# 4G_CAT1_CN4N40.net
KiCad netlist of a schematic drawn in Altium Designer
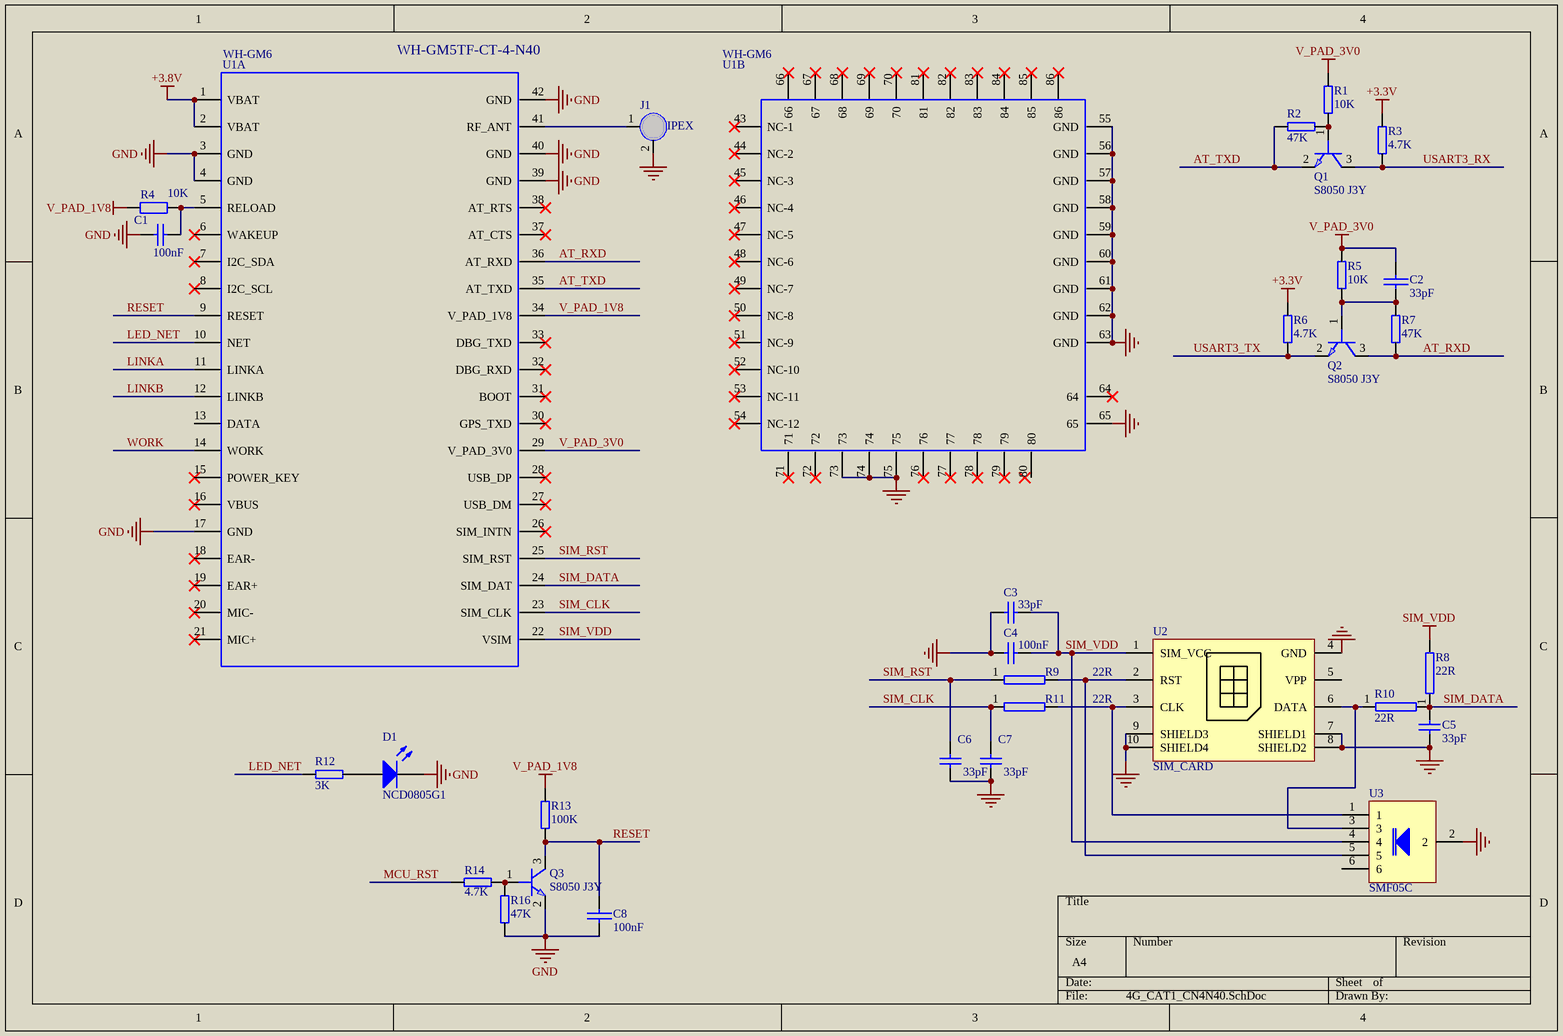
[diagram p0: 4G_CAT1_CN4N40.SchDoc]

(export (version "E")
  (design (tool "Eeschema 10.0.6"))
  (components
    (comp (ref "C1")
      (value "100nF")
      (footprint "LC-0805_C")
      (description "Capacitor")
      (fields (field (name "PUBLISHER") "Altium Limited"))
      (libsource (lib "*") (part "CAP"))
    )
    (comp (ref "C2")
      (value "33pF")
      (footprint "LC-0805_C")
      (description "Capacitor")
      (libsource (lib "") (part "CAP_1"))
    )
    (comp (ref "C3")
      (value "33pF")
      (footprint "LC-0805_C")
      (description "Capacitor")
      (fields (field (name "PUBLISHER") "Altium Limited"))
      (libsource (lib "*") (part "CAP"))
    )
    (comp (ref "C4")
      (value "100nF")
      (footprint "LC-0805_C")
      (description "Capacitor")
      (fields (field (name "PUBLISHER") "Altium Limited"))
      (libsource (lib "*") (part "CAP"))
    )
    (comp (ref "C5")
      (value "33pF")
      (footprint "LC-0805_C")
      (description "Capacitor")
      (fields (field (name "PUBLISHER") "Altium Limited"))
      (libsource (lib "*") (part "CAP"))
    )
    (comp (ref "C6")
      (value "33pF")
      (footprint "LC-0805_C")
      (description "Capacitor")
      (fields (field (name "PUBLISHER") "Altium Limited"))
      (libsource (lib "*") (part "CAP"))
    )
    (comp (ref "C7")
      (value "33pF")
      (footprint "LC-0805_C")
      (description "Capacitor")
      (fields (field (name "PUBLISHER") "Altium Limited"))
      (libsource (lib "*") (part "CAP"))
    )
    (comp (ref "C8")
      (value "100nF")
      (footprint "LC-0805_C")
      (description "Capacitor")
      (libsource (lib "") (part "CAP_1"))
    )
    (comp (ref "D1")
      (value "NCD0805G1")
      (footprint "LC-0805_LED_S1")
      (description "Typical RED, GREEN, YELLOW, AMBER GaAs LED")
      (fields (field (name "PUBLISHER") "Altium Limited"))
      (libsource (lib "Miscellaneous Devices") (part "LED2"))
    )
    (comp (ref "J1") (value "IPEX") (footprint "ANT-TH_KH-SMA-K513-G") (libsource (lib "NEW") (part "IPEX")))
    (comp (ref "Q1") (value "S8050 J3Y") (footprint "SOT-23") (libsource (lib "*") (part "2N5551")))
    (comp (ref "Q2") (value "S8050 J3Y") (footprint "SOT-23") (libsource (lib "*") (part "2N5551")))
    (comp (ref "Q3") (value "S8050 J3Y") (footprint "SOT-23") (libsource (lib "*") (part "2N5551")))
    (comp (ref "R1")
      (value "10K")
      (footprint "LC-0805_R")
      (description "1K")
      (libsource (lib "*") (part "RES22"))
    )
    (comp (ref "R2")
      (value "47K")
      (footprint "LC-0805_R")
      (description "1K")
      (libsource (lib "*") (part "RES22"))
    )
    (comp (ref "R3")
      (value "4.7K")
      (footprint "LC-0805_R")
      (description "1K")
      (libsource (lib "*") (part "RES22"))
    )
    (comp (ref "R4")
      (value "10K")
      (footprint "LC-0805_R")
      (description "Resistor")
      (fields (field (name "PUBLISHER") "Altium Limited"))
      (libsource (lib "Miscellaneous Devices") (part "Res2"))
    )
    (comp (ref "R5")
      (value "10K")
      (footprint "LC-0805_R")
      (description "1K")
      (libsource (lib "*") (part "RES22"))
    )
    (comp (ref "R6")
      (value "4.7K")
      (footprint "LC-0805_R")
      (description "1K")
      (libsource (lib "*") (part "RES22"))
    )
    (comp (ref "R7")
      (value "47K")
      (footprint "LC-0805_R")
      (description "1K")
      (libsource (lib "*") (part "RES22"))
    )
    (comp (ref "R8") (value "22R") (footprint "LC-0805_R") (libsource (lib "*") (part "RES2")))
    (comp (ref "R9") (value "22R") (footprint "LC-0805_R") (libsource (lib "*") (part "RES2")))
    (comp (ref "R10") (value "22R") (footprint "LC-0805_R") (libsource (lib "*") (part "RES2")))
    (comp (ref "R11") (value "22R") (footprint "LC-0805_R") (libsource (lib "*") (part "RES2")))
    (comp (ref "R12")
      (value "3K")
      (footprint "LC-0805_R")
      (description "1K")
      (libsource (lib "*") (part "RES22"))
    )
    (comp (ref "R13")
      (value "100K")
      (footprint "LC-0805_R")
      (description "1K")
      (libsource (lib "*") (part "RES22"))
    )
    (comp (ref "R14")
      (value "4.7K")
      (footprint "LC-0805_R")
      (description "1K")
      (libsource (lib "*") (part "RES22"))
    )
    (comp (ref "R16")
      (value "47K")
      (footprint "LC-0805_R")
      (description "1K")
      (libsource (lib "*") (part "RES22"))
    )
    (comp (ref "U1") (value "WH-GM6") (footprint "WH-GM6") (libsource (lib "WH-GM5TF-8-N40") (part "WH-GM6")))
    (comp (ref "U2")
      (value "SIM_CARD")
      (footprint "SIM_MICRO_6P")
      (libsource (lib "PCB_Project_gprs") (part "SIM_CARD"))
    )
    (comp (ref "U3") (value "SMF05C") (footprint "SOT-363") (libsource (lib "NEW") (part "SMF05C")))
  )
  (nets
    (net (code "1") (name "+3.3V") (class "Default")
      (node (ref "R3") (pin "1") (pintype "passive"))
      (node (ref "R6") (pin "1") (pintype "passive"))
    )
    (net (code "2") (name "+3.8V") (class "Default")
      (node (ref "U1") (pin "1") (pinfunction "VBAT_1") (pintype "passive"))
      (node (ref "U1") (pin "2") (pinfunction "VBAT_2") (pintype "passive"))
    )
    (net (code "3") (name "/AT_RXD") (class "Default")
      (node (ref "Q2") (pin "3") (pinfunction "C_3") (pintype "passive"))
      (node (ref "R7") (pin "1") (pintype "passive"))
      (node (ref "U1") (pin "36") (pinfunction "AT_RXD_36") (pintype "passive"))
    )
    (net (code "4") (name "/AT_TXD") (class "Default")
      (node (ref "Q1") (pin "2") (pinfunction "E_2") (pintype "passive"))
      (node (ref "R2") (pin "1") (pintype "passive"))
      (node (ref "U1") (pin "35") (pinfunction "AT_TXD_35") (pintype "passive"))
    )
    (net (code "5") (name "/LED_NET") (class "Default")
      (node (ref "R12") (pin "2") (pintype "passive"))
      (node (ref "U1") (pin "10") (pinfunction "NET_10") (pintype "passive"))
    )
    (net (code "6") (name "/LINKA") (class "Default")
      (node (ref "U1") (pin "11") (pinfunction "LINKA_11") (pintype "passive"))
    )
    (net (code "7") (name "/LINKB") (class "Default")
      (node (ref "U1") (pin "12") (pinfunction "LINKB_12") (pintype "passive"))
    )
    (net (code "8") (name "/MCU_RST") (class "Default") (node (ref "R14") (pin "1") (pintype "passive")))
    (net (code "9") (name "/RESET") (class "Default")
      (node (ref "C8") (pin "1") (pinfunction "1_1") (pintype "passive"))
      (node (ref "Q3") (pin "3") (pinfunction "C_3") (pintype "passive"))
      (node (ref "R13") (pin "1") (pintype "passive"))
      (node (ref "U1") (pin "9") (pinfunction "RESET_9") (pintype "passive"))
    )
    (net (code "10") (name "/SIM_CLK") (class "Default")
      (node (ref "C7") (pin "1") (pinfunction "1_1") (pintype "passive"))
      (node (ref "R11") (pin "1") (pintype "passive"))
      (node (ref "U1") (pin "23") (pinfunction "SIM_CLK_23") (pintype "passive"))
    )
    (net (code "11") (name "/SIM_DATA") (class "Default")
      (node (ref "C5") (pin "1") (pinfunction "1_1") (pintype "passive"))
      (node (ref "R10") (pin "2") (pintype "passive"))
      (node (ref "R8") (pin "1") (pintype "passive"))
      (node (ref "U1") (pin "24") (pinfunction "SIM_DAT_24") (pintype "passive"))
    )
    (net (code "12") (name "/SIM_RST") (class "Default")
      (node (ref "C6") (pin "1") (pinfunction "1_1") (pintype "passive"))
      (node (ref "R9") (pin "1") (pintype "passive"))
      (node (ref "U1") (pin "25") (pinfunction "SIM_RST_25") (pintype "passive"))
    )
    (net (code "13") (name "/USART3_RX") (class "Default")
      (node (ref "Q1") (pin "3") (pinfunction "C_3") (pintype "passive"))
      (node (ref "R3") (pin "2") (pintype "passive"))
    )
    (net (code "14") (name "/USART3_TX") (class "Default")
      (node (ref "Q2") (pin "2") (pinfunction "E_2") (pintype "passive"))
      (node (ref "R6") (pin "2") (pintype "passive"))
    )
    (net (code "15") (name "/WORK") (class "Default")
      (node (ref "U1") (pin "14") (pinfunction "WORK_14") (pintype "passive"))
    )
    (net (code "16") (name "GND") (class "Default")
      (node (ref "C1") (pin "1") (pinfunction "1_1") (pintype "passive"))
      (node (ref "C3") (pin "1") (pinfunction "1_1") (pintype "passive"))
      (node (ref "C4") (pin "1") (pinfunction "1_1") (pintype "passive"))
      (node (ref "C5") (pin "2") (pinfunction "2_2") (pintype "passive"))
      (node (ref "C6") (pin "2") (pinfunction "2_2") (pintype "passive"))
      (node (ref "C7") (pin "2") (pinfunction "2_2") (pintype "passive"))
      (node (ref "C8") (pin "2") (pinfunction "2_2") (pintype "passive"))
      (node (ref "D1") (pin "2") (pinfunction "K_2") (pintype "passive"))
      (node (ref "J1") (pin "2") (pinfunction "2_2") (pintype "passive"))
      (node (ref "Q3") (pin "2") (pinfunction "E_2") (pintype "passive"))
      (node (ref "R16") (pin "1") (pintype "passive"))
      (node (ref "U1") (pin "17") (pinfunction "GND_17") (pintype "passive"))
      (node (ref "U1") (pin "3") (pinfunction "GND_3") (pintype "passive"))
      (node (ref "U1") (pin "39") (pinfunction "GND_39") (pintype "passive"))
      (node (ref "U1") (pin "4") (pinfunction "GND_4") (pintype "passive"))
      (node (ref "U1") (pin "40") (pinfunction "GND_40") (pintype "passive"))
      (node (ref "U1") (pin "42") (pinfunction "GND_42") (pintype "passive"))
      (node (ref "U1") (pin "55") (pinfunction "GND_55") (pintype "passive"))
      (node (ref "U1") (pin "56") (pinfunction "GND_56") (pintype "passive"))
      (node (ref "U1") (pin "57") (pinfunction "GND_57") (pintype "passive"))
      (node (ref "U1") (pin "58") (pinfunction "GND_58") (pintype "passive"))
      (node (ref "U1") (pin "59") (pinfunction "GND_59") (pintype "passive"))
      (node (ref "U1") (pin "60") (pinfunction "GND_60") (pintype "passive"))
      (node (ref "U1") (pin "61") (pinfunction "GND_61") (pintype "passive"))
      (node (ref "U1") (pin "62") (pinfunction "GND_62") (pintype "passive"))
      (node (ref "U1") (pin "63") (pinfunction "GND_63") (pintype "passive"))
      (node (ref "U1") (pin "65") (pinfunction "65_65") (pintype "passive"))
      (node (ref "U1") (pin "73") (pinfunction "73_73") (pintype "passive"))
      (node (ref "U1") (pin "74") (pinfunction "74_74") (pintype "passive"))
      (node (ref "U1") (pin "75") (pinfunction "75_75") (pintype "passive"))
      (node (ref "U2") (pin "10") (pinfunction "SHIELD4_10") (pintype "passive"))
      (node (ref "U2") (pin "4") (pinfunction "GND_4") (pintype "passive"))
      (node (ref "U2") (pin "7") (pinfunction "SHIELD1_7") (pintype "passive"))
      (node (ref "U2") (pin "8") (pinfunction "SHIELD2_8") (pintype "passive"))
      (node (ref "U2") (pin "9") (pinfunction "SHIELD3_9") (pintype "passive"))
      (node (ref "U3") (pin "2") (pinfunction "2_2") (pintype "passive"))
    )
    (net (code "17") (name "Net-(D1-A)") (class "Default")
      (node (ref "D1") (pin "1") (pinfunction "A_1") (pintype "passive"))
      (node (ref "R12") (pin "1") (pintype "passive"))
    )
    (net (code "18") (name "Net-(Q1-B)") (class "Default")
      (node (ref "Q1") (pin "1") (pinfunction "B_1") (pintype "passive"))
      (node (ref "R1") (pin "2") (pintype "passive"))
      (node (ref "R2") (pin "2") (pintype "passive"))
    )
    (net (code "19") (name "Net-(Q2-B)") (class "Default")
      (node (ref "C2") (pin "2") (pinfunction "2_2") (pintype "passive"))
      (node (ref "Q2") (pin "1") (pinfunction "B_1") (pintype "passive"))
      (node (ref "R5") (pin "2") (pintype "passive"))
      (node (ref "R7") (pin "2") (pintype "passive"))
    )
    (net (code "20") (name "Net-(Q3-B)") (class "Default")
      (node (ref "Q3") (pin "1") (pinfunction "B_1") (pintype "passive"))
      (node (ref "R14") (pin "2") (pintype "passive"))
      (node (ref "R16") (pin "2") (pintype "passive"))
    )
    (net (code "21") (name "Net-(U1A-RELOAD)") (class "Default")
      (node (ref "C1") (pin "2") (pinfunction "2_2") (pintype "passive"))
      (node (ref "R4") (pin "1") (pinfunction "1_1") (pintype "passive"))
      (node (ref "U1") (pin "5") (pinfunction "RELOAD_5") (pintype "passive"))
    )
    (net (code "22") (name "Net-(U1A-RF_ANT)") (class "Default")
      (node (ref "J1") (pin "1") (pinfunction "1_1") (pintype "passive"))
      (node (ref "U1") (pin "41") (pinfunction "RF_ANT_41") (pintype "passive"))
    )
    (net (code "23") (name "Net-(U2-CLK)") (class "Default")
      (node (ref "R11") (pin "2") (pintype "passive"))
      (node (ref "U2") (pin "3") (pinfunction "CLK_3") (pintype "passive"))
      (node (ref "U3") (pin "1") (pinfunction "1_1") (pintype "passive"))
    )
    (net (code "24") (name "Net-(U2-DATA)") (class "Default")
      (node (ref "R10") (pin "1") (pintype "passive"))
      (node (ref "U2") (pin "6") (pinfunction "DATA_6") (pintype "passive"))
      (node (ref "U3") (pin "3") (pinfunction "3_3") (pintype "passive"))
    )
    (net (code "25") (name "Net-(U2-RST)") (class "Default")
      (node (ref "R9") (pin "2") (pintype "passive"))
      (node (ref "U2") (pin "2") (pinfunction "RST_2") (pintype "passive"))
      (node (ref "U3") (pin "5") (pinfunction "5_5") (pintype "passive"))
    )
    (net (code "26") (name "SIM_VDD") (class "Default")
      (node (ref "C3") (pin "2") (pinfunction "2_2") (pintype "passive"))
      (node (ref "C4") (pin "2") (pinfunction "2_2") (pintype "passive"))
      (node (ref "R8") (pin "2") (pintype "passive"))
      (node (ref "U1") (pin "22") (pinfunction "VSIM_22") (pintype "passive"))
      (node (ref "U2") (pin "1") (pinfunction "SIM_VCC_1") (pintype "passive"))
      (node (ref "U3") (pin "4") (pinfunction "4_4") (pintype "passive"))
    )
    (net (code "27") (name "V_PAD_1V8") (class "Default")
      (node (ref "R13") (pin "2") (pintype "passive"))
      (node (ref "R4") (pin "2") (pinfunction "2_2") (pintype "passive"))
      (node (ref "U1") (pin "34") (pinfunction "V_PAD_1V8_34") (pintype "passive"))
    )
    (net (code "28") (name "V_PAD_3V0") (class "Default")
      (node (ref "C2") (pin "1") (pinfunction "1_1") (pintype "passive"))
      (node (ref "R1") (pin "1") (pintype "passive"))
      (node (ref "R5") (pin "1") (pintype "passive"))
      (node (ref "U1") (pin "29") (pinfunction "V_PAD_3V0_29") (pintype "passive"))
    )
    (net (code "29") (name "unconnected-(U1-Pad64)") (class "Default")
      (node (ref "U1") (pin "64") (pinfunction "64_64") (pintype "passive+no_connect"))
    )
    (net (code "30") (name "unconnected-(U1-Pad66)") (class "Default")
      (node (ref "U1") (pin "66") (pinfunction "66_66") (pintype "passive+no_connect"))
    )
    (net (code "31") (name "unconnected-(U1-Pad67)") (class "Default")
      (node (ref "U1") (pin "67") (pinfunction "67_67") (pintype "passive+no_connect"))
    )
    (net (code "32") (name "unconnected-(U1-Pad68)") (class "Default")
      (node (ref "U1") (pin "68") (pinfunction "68_68") (pintype "passive+no_connect"))
    )
    (net (code "33") (name "unconnected-(U1-Pad69)") (class "Default")
      (node (ref "U1") (pin "69") (pinfunction "69_69") (pintype "passive+no_connect"))
    )
    (net (code "34") (name "unconnected-(U1-Pad70)") (class "Default")
      (node (ref "U1") (pin "70") (pinfunction "70_70") (pintype "passive+no_connect"))
    )
    (net (code "35") (name "unconnected-(U1-Pad71)") (class "Default")
      (node (ref "U1") (pin "71") (pinfunction "71_71") (pintype "passive+no_connect"))
    )
    (net (code "36") (name "unconnected-(U1-Pad72)") (class "Default")
      (node (ref "U1") (pin "72") (pinfunction "72_72") (pintype "passive+no_connect"))
    )
    (net (code "37") (name "unconnected-(U1-Pad76)") (class "Default")
      (node (ref "U1") (pin "76") (pinfunction "76_76") (pintype "passive+no_connect"))
    )
    (net (code "38") (name "unconnected-(U1-Pad77)") (class "Default")
      (node (ref "U1") (pin "77") (pinfunction "77_77") (pintype "passive+no_connect"))
    )
    (net (code "39") (name "unconnected-(U1-Pad78)") (class "Default")
      (node (ref "U1") (pin "78") (pinfunction "78_78") (pintype "passive+no_connect"))
    )
    (net (code "40") (name "unconnected-(U1-Pad79)") (class "Default")
      (node (ref "U1") (pin "79") (pinfunction "79_79") (pintype "passive+no_connect"))
    )
    (net (code "41") (name "unconnected-(U1-Pad80)") (class "Default")
      (node (ref "U1") (pin "80") (pinfunction "80_80") (pintype "passive"))
    )
    (net (code "42") (name "unconnected-(U1-Pad81)") (class "Default")
      (node (ref "U1") (pin "81") (pinfunction "81_81") (pintype "passive+no_connect"))
    )
    (net (code "43") (name "unconnected-(U1-Pad82)") (class "Default")
      (node (ref "U1") (pin "82") (pinfunction "82_82") (pintype "passive+no_connect"))
    )
    (net (code "44") (name "unconnected-(U1-Pad83)") (class "Default")
      (node (ref "U1") (pin "83") (pinfunction "83_83") (pintype "passive+no_connect"))
    )
    (net (code "45") (name "unconnected-(U1-Pad84)") (class "Default")
      (node (ref "U1") (pin "84") (pinfunction "84_84") (pintype "passive+no_connect"))
    )
    (net (code "46") (name "unconnected-(U1-Pad85)") (class "Default")
      (node (ref "U1") (pin "85") (pinfunction "85_85") (pintype "passive+no_connect"))
    )
    (net (code "47") (name "unconnected-(U1-Pad86)") (class "Default")
      (node (ref "U1") (pin "86") (pinfunction "86_86") (pintype "passive+no_connect"))
    )
    (net (code "48") (name "unconnected-(U1A-AT_CTS-Pad37)") (class "Default")
      (node (ref "U1") (pin "37") (pinfunction "AT_CTS_37") (pintype "passive+no_connect"))
    )
    (net (code "49") (name "unconnected-(U1A-AT_RTS-Pad38)") (class "Default")
      (node (ref "U1") (pin "38") (pinfunction "AT_RTS_38") (pintype "passive+no_connect"))
    )
    (net (code "50") (name "unconnected-(U1A-BOOT-Pad31)") (class "Default")
      (node (ref "U1") (pin "31") (pinfunction "BOOT_31") (pintype "passive+no_connect"))
    )
    (net (code "51") (name "unconnected-(U1A-DATA-Pad13)") (class "Default")
      (node (ref "U1") (pin "13") (pinfunction "DATA_13") (pintype "passive"))
    )
    (net (code "52") (name "unconnected-(U1A-DBG_RXD-Pad32)") (class "Default")
      (node (ref "U1") (pin "32") (pinfunction "DBG_RXD_32") (pintype "passive+no_connect"))
    )
    (net (code "53") (name "unconnected-(U1A-DBG_TXD-Pad33)") (class "Default")
      (node (ref "U1") (pin "33") (pinfunction "DBG_TXD_33") (pintype "passive+no_connect"))
    )
    (net (code "54") (name "unconnected-(U1A-EAR+-Pad19)") (class "Default")
      (node (ref "U1") (pin "19") (pinfunction "EAR+_19") (pintype "passive+no_connect"))
    )
    (net (code "55") (name "unconnected-(U1A-EAR--Pad18)") (class "Default")
      (node (ref "U1") (pin "18") (pinfunction "EAR-_18") (pintype "passive+no_connect"))
    )
    (net (code "56") (name "unconnected-(U1A-GPS_TXD-Pad30)") (class "Default")
      (node (ref "U1") (pin "30") (pinfunction "GPS_TXD_30") (pintype "passive+no_connect"))
    )
    (net (code "57") (name "unconnected-(U1A-I2C_SCL-Pad8)") (class "Default")
      (node (ref "U1") (pin "8") (pinfunction "I2C_SCL_8") (pintype "passive+no_connect"))
    )
    (net (code "58") (name "unconnected-(U1A-I2C_SDA-Pad7)") (class "Default")
      (node (ref "U1") (pin "7") (pinfunction "I2C_SDA_7") (pintype "passive+no_connect"))
    )
    (net (code "59") (name "unconnected-(U1A-MIC+-Pad21)") (class "Default")
      (node (ref "U1") (pin "21") (pinfunction "MIC+_21") (pintype "passive+no_connect"))
    )
    (net (code "60") (name "unconnected-(U1A-MIC--Pad20)") (class "Default")
      (node (ref "U1") (pin "20") (pinfunction "MIC-_20") (pintype "passive+no_connect"))
    )
    (net (code "61") (name "unconnected-(U1A-POWER_KEY-Pad15)") (class "Default")
      (node (ref "U1") (pin "15") (pinfunction "POWER_KEY_15") (pintype "passive+no_connect"))
    )
    (net (code "62") (name "unconnected-(U1A-SIM_INTN-Pad26)") (class "Default")
      (node (ref "U1") (pin "26") (pinfunction "SIM_INTN_26") (pintype "passive+no_connect"))
    )
    (net (code "63") (name "unconnected-(U1A-USB_DM-Pad27)") (class "Default")
      (node (ref "U1") (pin "27") (pinfunction "USB_DM_27") (pintype "passive+no_connect"))
    )
    (net (code "64") (name "unconnected-(U1A-USB_DP-Pad28)") (class "Default")
      (node (ref "U1") (pin "28") (pinfunction "USB_DP_28") (pintype "passive+no_connect"))
    )
    (net (code "65") (name "unconnected-(U1A-VBUS-Pad16)") (class "Default")
      (node (ref "U1") (pin "16") (pinfunction "VBUS_16") (pintype "passive+no_connect"))
    )
    (net (code "66") (name "unconnected-(U1A-WAKEUP-Pad6)") (class "Default")
      (node (ref "U1") (pin "6") (pinfunction "WAKEUP_6") (pintype "passive+no_connect"))
    )
    (net (code "67") (name "unconnected-(U1B-NC-1-Pad43)") (class "Default")
      (node (ref "U1") (pin "43") (pinfunction "NC-1_43") (pintype "passive+no_connect"))
    )
    (net (code "68") (name "unconnected-(U1B-NC-2-Pad44)") (class "Default")
      (node (ref "U1") (pin "44") (pinfunction "NC-2_44") (pintype "passive+no_connect"))
    )
    (net (code "69") (name "unconnected-(U1B-NC-3-Pad45)") (class "Default")
      (node (ref "U1") (pin "45") (pinfunction "NC-3_45") (pintype "passive+no_connect"))
    )
    (net (code "70") (name "unconnected-(U1B-NC-4-Pad46)") (class "Default")
      (node (ref "U1") (pin "46") (pinfunction "NC-4_46") (pintype "passive+no_connect"))
    )
    (net (code "71") (name "unconnected-(U1B-NC-5-Pad47)") (class "Default")
      (node (ref "U1") (pin "47") (pinfunction "NC-5_47") (pintype "passive+no_connect"))
    )
    (net (code "72") (name "unconnected-(U1B-NC-6-Pad48)") (class "Default")
      (node (ref "U1") (pin "48") (pinfunction "NC-6_48") (pintype "passive+no_connect"))
    )
    (net (code "73") (name "unconnected-(U1B-NC-7-Pad49)") (class "Default")
      (node (ref "U1") (pin "49") (pinfunction "NC-7_49") (pintype "passive+no_connect"))
    )
    (net (code "74") (name "unconnected-(U1B-NC-8-Pad50)") (class "Default")
      (node (ref "U1") (pin "50") (pinfunction "NC-8_50") (pintype "passive+no_connect"))
    )
    (net (code "75") (name "unconnected-(U1B-NC-9-Pad51)") (class "Default")
      (node (ref "U1") (pin "51") (pinfunction "NC-9_51") (pintype "passive+no_connect"))
    )
    (net (code "76") (name "unconnected-(U1B-NC-10-Pad52)") (class "Default")
      (node (ref "U1") (pin "52") (pinfunction "NC-10_52") (pintype "passive+no_connect"))
    )
    (net (code "77") (name "unconnected-(U1B-NC-11-Pad53)") (class "Default")
      (node (ref "U1") (pin "53") (pinfunction "NC-11_53") (pintype "passive+no_connect"))
    )
    (net (code "78") (name "unconnected-(U1B-NC-12-Pad54)") (class "Default")
      (node (ref "U1") (pin "54") (pinfunction "NC-12_54") (pintype "passive+no_connect"))
    )
    (net (code "79") (name "unconnected-(U2-VPP-Pad5)") (class "Default")
      (node (ref "U2") (pin "5") (pinfunction "VPP_5") (pintype "passive"))
    )
    (net (code "80") (name "unconnected-(U3-Pad6)") (class "Default")
      (node (ref "U3") (pin "6") (pinfunction "6_6") (pintype "passive"))
    )
  )
)
